# 01_NRF52.net
KiCad netlist of a schematic drawn in Altium Designer
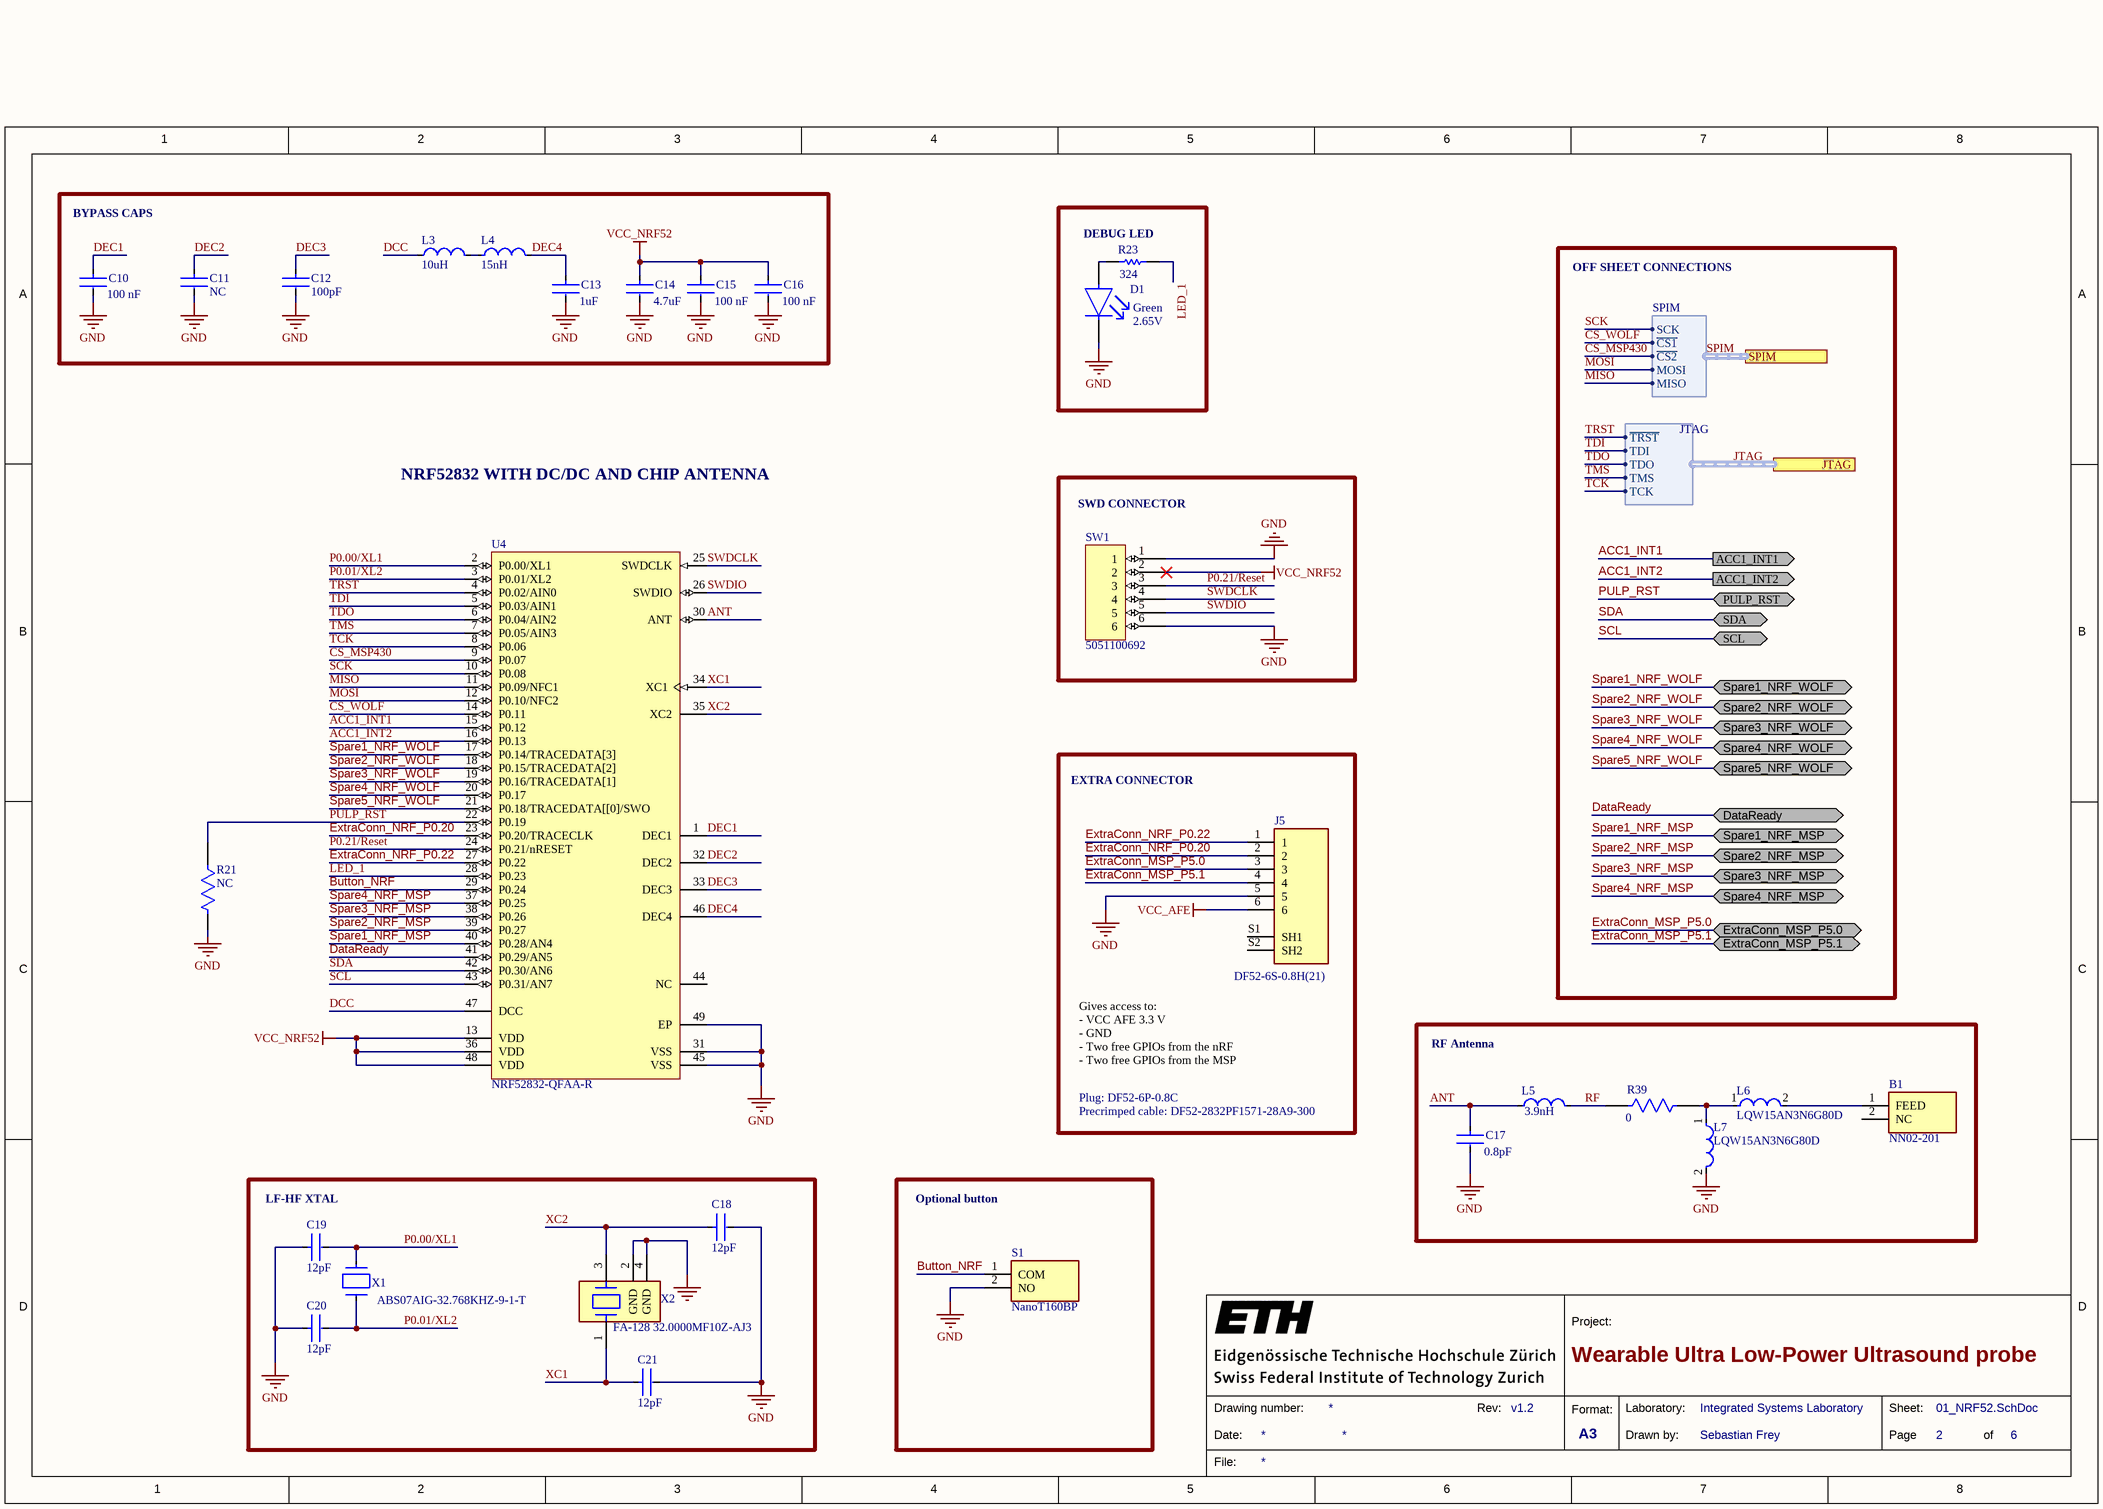
[diagram p0: 01_NRF52.SchDoc]

(export (version "E")
  (design (tool "Eeschema 10.0.6"))
  (components
    (comp (ref "B1")
      (value "NN02-201")
      (footprint "NN02201")
      (description "RF ANTENNA 2G, 3G, 4G, 5G, DCS, GSM, LTE, PCS, UMTS, Wifi DB Chip SMA Surface Mount")
      (fields (field (name "MOUSER PART NUMBER") "128-NN02-201"))
      (libsource (lib "Schlib1") (part "NN02-201"))
    )
    (comp (ref "C10")
      (value "100 nF")
      (footprint "FP-CC0402-MFG")
      (description "CAP CER 0.1UF 16V X7R 0402")
      (fields (field (name "MANUFACTURER") "YAGEO") (field (name "TOLERANCE") "0.1"))
      (libsource (lib "Altium Content Vault") (part "11868f565c42a9108669ba33697ecf6"))
    )
    (comp (ref "C11")
      (value "not mounted")
      (footprint "FP-04025A101JAT2A-MFG")
      (fields
        (field (name "TOLERANCE") "5%")
        (field (name "VOLTAGE") "50V")
        (field (name "CAPACITANCE") "NC")
      )
      (libsource (lib "Altium Content Vault") (part "f23184f103b6ebe33a8c269c53dcba6"))
    )
    (comp (ref "C12")
      (value "04025A101JAT2A")
      (footprint "FP-04025A101JAT2A-MFG")
      (description "CAP CER 100PF 50V C0G/NP0 0402")
      (fields
        (field (name "TOLERANCE") "5%")
        (field (name "VOLTAGE") "50V")
        (field (name "CAPACITANCE") "100pF")
      )
      (libsource (lib "Altium Content Vault") (part "f23184f103b6ebe33a8c269c53dcba6"))
    )
    (comp (ref "C13")
      (value "C1608X7R1C105K080AC")
      (footprint "FP-C1608-080-0_1-IPC_B")
      (description "Multilayer Ceramic Capacitors 1μF ±10% 16V X7R SMD 0603")
      (fields
        (field (name "VOLTAGE") "16V")
        (field (name "CAPACITANCE") "1uF")
        (field (name "TOLERANCE") "10%")
      )
      (libsource (lib "Altium Content Vault") (part "236180d848d6139a670b325ea6854c9"))
    )
    (comp (ref "C14")
      (value "EMK107ABJ475KA-T")
      (footprint "FP-0603-L_1_6_0_15-W_0_8-IPC_A")
      (description "None")
      (fields (field (name "CAPACITANCE") "4.7uF") (field (name "TOLERANCE") "10%"))
      (libsource (lib "Altium Content Vault") (part "11868f565c42a9108669ba33697ecf6"))
    )
    (comp (ref "C15")
      (value "100 nF")
      (footprint "FP-CC0402-MFG")
      (description "CAP CER 0.1UF 16V X7R 0402")
      (fields (field (name "MANUFACTURER") "YAGEO") (field (name "TOLERANCE") "0.1"))
      (libsource (lib "Altium Content Vault") (part "11868f565c42a9108669ba33697ecf6"))
    )
    (comp (ref "C16")
      (value "100 nF")
      (footprint "FP-CC0402-MFG")
      (description "CAP CER 0.1UF 16V X7R 0402")
      (fields (field (name "MANUFACTURER") "YAGEO") (field (name "TOLERANCE") "0.1"))
      (libsource (lib "Altium Content Vault") (part "11868f565c42a9108669ba33697ecf6"))
    )
    (comp (ref "C17")
      (value "GJM1555C1HR80WB01D")
      (footprint "FP-GJM155-0_05-IPC_A")
      (description "Multi-Layer Ceramic Capacitor 0.8pF C0G  ±0.05pF 0402 Paper T/R")
      (fields (field (name "CAPACITANCE") "0.8pF"))
      (libsource (lib "Altium Content Vault") (part "02cd4be3c70576c341d710602a673aa"))
    )
    (comp (ref "C18")
      (value "GJM1555C1H120GB01D")
      (footprint "FP-GJM155-0_05-IPC_A")
      (description "Multi-Layer Ceramic Capacitor 12pF C0G  ±2% 0402 Paper T/R")
      (fields (field (name "TOLERANCE") "2%") (field (name "CAPACITANCE") "12pF"))
      (libsource (lib "Altium Content Vault") (part "02cd4be3c70576c341d710602a673aa"))
    )
    (comp (ref "C19")
      (value "GJM1555C1H120GB01D")
      (footprint "FP-GJM155-0_05-IPC_A")
      (description "Multi-Layer Ceramic Capacitor 12pF C0G  ±2% 0402 Paper T/R")
      (fields (field (name "TOLERANCE") "2%") (field (name "CAPACITANCE") "12pF"))
      (libsource (lib "Altium Content Vault") (part "02cd4be3c70576c341d710602a673aa"))
    )
    (comp (ref "C20")
      (value "GJM1555C1H120GB01D")
      (footprint "FP-GJM155-0_05-IPC_A")
      (description "Multi-Layer Ceramic Capacitor 12pF C0G  ±2% 0402 Paper T/R")
      (fields (field (name "TOLERANCE") "2%") (field (name "CAPACITANCE") "12pF"))
      (libsource (lib "Altium Content Vault") (part "02cd4be3c70576c341d710602a673aa"))
    )
    (comp (ref "C21")
      (value "GJM1555C1H120GB01D")
      (footprint "FP-GJM155-0_05-IPC_A")
      (description "Multi-Layer Ceramic Capacitor 12pF C0G  ±2% 0402 Paper T/R")
      (fields (field (name "TOLERANCE") "2%") (field (name "CAPACITANCE") "12pF"))
      (libsource (lib "Altium Content Vault") (part "02cd4be3c70576c341d710602a673aa"))
    )
    (comp (ref "D1")
      (value "APHD1608LZGCK")
      (footprint "FP-APHD1608LZGCK-MFG")
      (description "LED GREEN CLEAR 1608 SMD")
      (fields (field (name "FORWARD VOLTAGE") "2.65V") (field (name "COLOR") "Green"))
      (libsource (lib "Altium Content Vault") (part "8706943c75ba83719d021d2fdc84c58"))
    )
    (comp (ref "J5")
      (value "DF52-6S-0.8H(21)")
      (footprint "PcbLib1:HIROSE_DF52-6S-0.8H(21)")
      (description "6 Position Socket Connector Surface Mount, Right Angle")
      (fields (field (name "MP") "DF52-6S-0.8H_21_") (field (name "MF") "Hirose"))
      (libsource (lib "Schlib1") (part "DF52-6S-0.8H(21)"))
    )
    (comp (ref "L3")
      (value "L0603B100KDWFT")
      (footprint "PcbLib1:L0603B100KDWFT")
      (description "Inductor RF Chip Wirewound 10uH 10% 2.52MHz 0.38A 0.36Ohm DCR 0603 T/R")
      (fields
        (field (name "MANUFACTURER") "KEMET")
        (field (name "TOLERANCE") "10%")
        (field (name "INDUCTANCE") "10uH")
      )
      (libsource (lib "Schlib1") (part "L0603B100KDWFT"))
    )
    (comp (ref "L4")
      (value "LQW15AN15NJ00D")
      (footprint "FP-LQW15AN_00-W0_6-0_1-MFG")
      (description "Wire Wound RF Inductor 15nH ±5% 460mA 0.16Ω 0402 (1005)")
      (fields (field (name "INDUCTANCE") "15nH") (field (name "TOLERANCE") "5%"))
      (libsource (lib "Altium Content Vault") (part "725321dda6339637d4d059423bc1c3c"))
    )
    (comp (ref "L5")
      (value "LQG15HS3N9B02D")
      (footprint "PcbLib1:INDC1005X45N")
      (description "Inductor RF Chip Thin Film 3.9nH 0.1nH 500MHz 13Q-Factor 170mA 500mOhm DCR 0402 Paper T/R")
      (fields
        (field (name "MANUFACTURER") "Murata")
        (field (name "MANUFACTURER PART NUMBER") "LQP15MN3N9B02D")
        (field (name "INDUCTANCE") "3.9nH")
      )
      (libsource (lib "Schlib1") (part "LQP15MN3N9B02D"))
    )
    (comp (ref "L6")
      (value "LQW15AN3N6G80D")
      (footprint "PcbLib1:Component_0402_0603")
      (description "Wire Wound RF Inductor 3.6nH ±2% 1950mA 0.03Ω 0402 (1005)")
      (libsource (lib "Schlib1") (part "725321dda6339637d4d059423bc1c3c"))
    )
    (comp (ref "L7")
      (value "LQW15AN3N6G80D")
      (footprint "PcbLib1:Component_0402_0603")
      (description "Wire Wound RF Inductor 3.6nH ±2% 1950mA 0.03Ω 0402 (1005)")
      (libsource (lib "Schlib1") (part "725321dda6339637d4d059423bc1c3c"))
    )
    (comp (ref "R21")
      (value "~")
      (footprint "FP-ERJ2RK-IPC_C")
      (description "not mounted")
      (fields (field (name "RESISTANCE") "NC") (field (name "TOLERANCE") "1%"))
      (libsource (lib "Altium Content Vault") (part "1029c3af85768c4190bb7ad29bc67b5"))
    )
    (comp (ref "R23")
      (value "CPF0402B324RE1")
      (footprint "RESC1005X35X20ML05T10")
      (fields (field (name "MANUFACTURER") "TE Connectivity / AMP") (field (name "RESISTANCE") "324"))
      (libsource (lib "Altium Content Vault") (part "RES"))
    )
    (comp (ref "R39")
      (value "CR0402-J/-000GLF")
      (footprint "PcbLib1:Component_0402_0603")
      (description "Thick Film Chip Resistors 0402 0Ω 0.0625W 5%")
      (fields (field (name "TOLERANCE") "5%") (field (name "RESISTANCE") "0"))
      (libsource (lib "Schlib1") (part "1029c3af85768c4190bb7ad29bc67b5"))
    )
    (comp (ref "S1")
      (value "NanoT160BP")
      (footprint "PcbLib1:NanoT160BP")
      (description "Switch")
      (libsource (lib "Schlib1") (part "NanoT160BP"))
    )
    (comp (ref "SW1")
      (value "5051100692")
      (footprint "PcbLib1:MOLEX_5051100692")
      (libsource (lib "Schlib1") (part "MOLEX_5051100692"))
    )
    (comp (ref "U4")
      (value "NRF52832-QFAA-R")
      (footprint "NRSC-QF-48_M")
      (fields (field (name "MANUFACTURER") "Nordic Semiconductor"))
      (libsource (lib "Altium Content Vault") (part "NRSC-NRF52832-QF-48"))
    )
    (comp (ref "X1")
      (value "ABS07AIG-32.768KHZ-9-1-T")
      (footprint "PcbLib1:Crys_Abracon_ABS07AIG-32_768KHZ-9-1-T_eec_MFG")
      (description "Crystal")
      (libsource (lib "Schlib1") (part "Crys_Abracon_ABS07AIG-32_768KHZ-9-1-T_eec"))
    )
    (comp (ref "X2")
      (value "FA-128 32.0000MF10Z-AJ3")
      (footprint "PcbLib1:Crys_Seiko_Epson_Corporation_FA-128_32.0000MF10Z-AJ3_eec_0")
      (description "Crystal")
      (fields (field (name "PART NR") "FA-128 32.0000MF10Z-AJ3"))
      (libsource (lib "Schlib1") (part "Crys_Seiko_Epson_Corporation_FA-128_32.0000MF10Z-AJ3_eec"))
    )
  )
  (nets
    (net (code "3") (name "/ACC1_INT1") (class "Default")
      (node (ref "U4") (pin "15") (pinfunction "P0.12_15") (pintype "bidirectional"))
    )
    (net (code "4") (name "/ACC1_INT2") (class "Default")
      (node (ref "U4") (pin "16") (pinfunction "P0.13_16") (pintype "bidirectional"))
    )
    (net (code "5") (name "/ANT") (class "Default")
      (node (ref "C17") (pin "1") (pinfunction "1_1") (pintype "passive"))
      (node (ref "L5") (pin "1") (pinfunction "1_1") (pintype "passive"))
      (node (ref "U4") (pin "30") (pinfunction "ANT_30") (pintype "bidirectional"))
    )
    (net (code "6") (name "/Button_NRF") (class "Default")
      (node (ref "S1") (pin "1") (pinfunction "COM_1") (pintype "passive"))
      (node (ref "U4") (pin "29") (pinfunction "P0.24_29") (pintype "bidirectional"))
    )
    (net (code "7") (name "/CS_MSP430") (class "Default")
      (node (ref "U4") (pin "9") (pinfunction "P0.07_9") (pintype "bidirectional"))
    )
    (net (code "8") (name "/CS_WOLF") (class "Default")
      (node (ref "U4") (pin "14") (pinfunction "P0.11_14") (pintype "bidirectional"))
    )
    (net (code "9") (name "/DCC") (class "Default")
      (node (ref "L3") (pin "1") (pinfunction "1_1") (pintype "passive"))
      (node (ref "U4") (pin "47") (pinfunction "DCC_47") (pintype "power_in"))
    )
    (net (code "10") (name "/DEC1") (class "Default")
      (node (ref "C10") (pin "1") (pinfunction "1_1") (pintype "passive"))
      (node (ref "U4") (pin "1") (pinfunction "DEC1_1") (pintype "passive"))
    )
    (net (code "11") (name "/DEC2") (class "Default")
      (node (ref "C11") (pin "2") (pinfunction "2_2") (pintype "passive"))
      (node (ref "U4") (pin "32") (pinfunction "DEC2_32") (pintype "passive"))
    )
    (net (code "12") (name "/DEC3") (class "Default")
      (node (ref "C12") (pin "2") (pinfunction "2_2") (pintype "passive"))
      (node (ref "U4") (pin "33") (pinfunction "DEC3_33") (pintype "passive"))
    )
    (net (code "13") (name "/DEC4") (class "Default")
      (node (ref "C13") (pin "2") (pinfunction "2_2") (pintype "passive"))
      (node (ref "L4") (pin "2") (pinfunction "2_2") (pintype "passive"))
      (node (ref "U4") (pin "46") (pinfunction "DEC4_46") (pintype "passive"))
    )
    (net (code "14") (name "/DataReady") (class "Default")
      (node (ref "U4") (pin "41") (pinfunction "P0.29/AN5_41") (pintype "bidirectional"))
    )
    (net (code "15") (name "/ExtraConn_MSP_P5.0") (class "Default")
      (node (ref "J5") (pin "3") (pinfunction "3_3") (pintype "passive"))
    )
    (net (code "16") (name "/ExtraConn_MSP_P5.1") (class "Default")
      (node (ref "J5") (pin "4") (pinfunction "4_4") (pintype "passive"))
    )
    (net (code "17") (name "/ExtraConn_NRF_P0.20") (class "Default")
      (node (ref "J5") (pin "2") (pinfunction "2_2") (pintype "passive"))
      (node (ref "U4") (pin "23") (pinfunction "P0.20/TRACECLK_23") (pintype "bidirectional"))
    )
    (net (code "18") (name "/ExtraConn_NRF_P0.22") (class "Default")
      (node (ref "J5") (pin "1") (pinfunction "1_1") (pintype "passive"))
      (node (ref "U4") (pin "27") (pinfunction "P0.22_27") (pintype "bidirectional"))
    )
    (net (code "20") (name "/LED_1") (class "Default")
      (node (ref "R23") (pin "1") (pinfunction "1_1") (pintype "passive"))
      (node (ref "U4") (pin "28") (pinfunction "P0.23_28") (pintype "bidirectional"))
    )
    (net (code "21") (name "/MISO") (class "Default")
      (node (ref "U4") (pin "11") (pinfunction "P0.09/NFC1_11") (pintype "bidirectional"))
    )
    (net (code "22") (name "/MOSI") (class "Default")
      (node (ref "U4") (pin "12") (pinfunction "P0.10/NFC2_12") (pintype "bidirectional"))
    )
    (net (code "23") (name "/P0.00{slash}XL1") (class "Default")
      (node (ref "C19") (pin "2") (pinfunction "2_2") (pintype "passive"))
      (node (ref "U4") (pin "2") (pinfunction "P0.00/XL1_2") (pintype "bidirectional"))
      (node (ref "X1") (pin "1") (pinfunction "1_1") (pintype "passive"))
    )
    (net (code "24") (name "/P0.01{slash}XL2") (class "Default")
      (node (ref "C20") (pin "2") (pinfunction "2_2") (pintype "passive"))
      (node (ref "U4") (pin "3") (pinfunction "P0.01/XL2_3") (pintype "bidirectional"))
      (node (ref "X1") (pin "2") (pinfunction "2_2") (pintype "passive"))
    )
    (net (code "25") (name "/P0.21{slash}Reset") (class "Default")
      (node (ref "SW1") (pin "3") (pinfunction "3_3") (pintype "bidirectional"))
      (node (ref "U4") (pin "24") (pinfunction "P0.21/nRESET_24") (pintype "bidirectional"))
    )
    (net (code "26") (name "/PULP_RST") (class "Default")
      (node (ref "R21") (pin "1") (pinfunction "1_1") (pintype "passive"))
      (node (ref "U4") (pin "22") (pinfunction "P0.19_22") (pintype "bidirectional"))
    )
    (net (code "27") (name "/RF") (class "Default")
      (node (ref "L5") (pin "2") (pinfunction "2_2") (pintype "passive"))
      (node (ref "R39") (pin "1") (pinfunction "1_1") (pintype "passive"))
    )
    (net (code "28") (name "/SCK") (class "Default")
      (node (ref "U4") (pin "10") (pinfunction "P0.08_10") (pintype "bidirectional"))
    )
    (net (code "29") (name "/SCL") (class "Default")
      (node (ref "U4") (pin "43") (pinfunction "P0.31/AN7_43") (pintype "bidirectional"))
    )
    (net (code "30") (name "/SDA") (class "Default")
      (node (ref "U4") (pin "42") (pinfunction "P0.30/AN6_42") (pintype "bidirectional"))
    )
    (net (code "32") (name "/SWDCLK") (class "Default")
      (node (ref "SW1") (pin "4") (pinfunction "4_4") (pintype "bidirectional"))
      (node (ref "U4") (pin "25") (pinfunction "SWDCLK_25") (pintype "input"))
    )
    (net (code "33") (name "/SWDIO") (class "Default")
      (node (ref "SW1") (pin "5") (pinfunction "5_5") (pintype "bidirectional"))
      (node (ref "U4") (pin "26") (pinfunction "SWDIO_26") (pintype "bidirectional"))
    )
    (net (code "34") (name "/Spare1_NRF_MSP") (class "Default")
      (node (ref "U4") (pin "40") (pinfunction "P0.28/AN4_40") (pintype "bidirectional"))
    )
    (net (code "35") (name "/Spare1_NRF_WOLF") (class "Default")
      (node (ref "U4") (pin "17") (pinfunction "P0.14/TRACEDATA[3]_17") (pintype "bidirectional"))
    )
    (net (code "36") (name "/Spare2_NRF_MSP") (class "Default")
      (node (ref "U4") (pin "39") (pinfunction "P0.27_39") (pintype "bidirectional"))
    )
    (net (code "37") (name "/Spare2_NRF_WOLF") (class "Default")
      (node (ref "U4") (pin "18") (pinfunction "P0.15/TRACEDATA[2]_18") (pintype "bidirectional"))
    )
    (net (code "38") (name "/Spare3_NRF_MSP") (class "Default")
      (node (ref "U4") (pin "38") (pinfunction "P0.26_38") (pintype "bidirectional"))
    )
    (net (code "39") (name "/Spare3_NRF_WOLF") (class "Default")
      (node (ref "U4") (pin "19") (pinfunction "P0.16/TRACEDATA[1]_19") (pintype "bidirectional"))
    )
    (net (code "40") (name "/Spare4_NRF_MSP") (class "Default")
      (node (ref "U4") (pin "37") (pinfunction "P0.25_37") (pintype "bidirectional"))
    )
    (net (code "41") (name "/Spare4_NRF_WOLF") (class "Default")
      (node (ref "U4") (pin "20") (pinfunction "P0.17_20") (pintype "bidirectional"))
    )
    (net (code "42") (name "/Spare5_NRF_WOLF") (class "Default")
      (node (ref "U4") (pin "21") (pinfunction "P0.18/TRACEDATA[[0]/SWO_21") (pintype "bidirectional"))
    )
    (net (code "43") (name "/TCK") (class "Default")
      (node (ref "U4") (pin "8") (pinfunction "P0.06_8") (pintype "bidirectional"))
    )
    (net (code "44") (name "/TDI") (class "Default")
      (node (ref "U4") (pin "5") (pinfunction "P0.03/AIN1_5") (pintype "bidirectional"))
    )
    (net (code "45") (name "/TDO") (class "Default")
      (node (ref "U4") (pin "6") (pinfunction "P0.04/AIN2_6") (pintype "bidirectional"))
    )
    (net (code "46") (name "/TMS") (class "Default")
      (node (ref "U4") (pin "7") (pinfunction "P0.05/AIN3_7") (pintype "bidirectional"))
    )
    (net (code "47") (name "/TRST") (class "Default")
      (node (ref "U4") (pin "4") (pinfunction "P0.02/AIN0_4") (pintype "bidirectional"))
    )
    (net (code "48") (name "/XC1") (class "Default")
      (node (ref "C21") (pin "1") (pinfunction "1_1") (pintype "passive"))
      (node (ref "U4") (pin "34") (pinfunction "XC1_34") (pintype "input"))
      (node (ref "X2") (pin "1") (pinfunction "1_1") (pintype "passive"))
    )
    (net (code "49") (name "/XC2") (class "Default")
      (node (ref "C18") (pin "1") (pinfunction "1_1") (pintype "passive"))
      (node (ref "U4") (pin "35") (pinfunction "XC2_35") (pintype "passive"))
      (node (ref "X2") (pin "3") (pinfunction "3_3") (pintype "passive"))
    )
    (net (code "50") (name "GND") (class "Default")
      (node (ref "C10") (pin "2") (pinfunction "2_2") (pintype "passive"))
      (node (ref "C11") (pin "1") (pinfunction "1_1") (pintype "passive"))
      (node (ref "C12") (pin "1") (pinfunction "1_1") (pintype "passive"))
      (node (ref "C13") (pin "1") (pinfunction "1_1") (pintype "passive"))
      (node (ref "C14") (pin "2") (pinfunction "2_2") (pintype "passive"))
      (node (ref "C15") (pin "2") (pinfunction "2_2") (pintype "passive"))
      (node (ref "C16") (pin "2") (pinfunction "2_2") (pintype "passive"))
      (node (ref "C17") (pin "2") (pinfunction "2_2") (pintype "passive"))
      (node (ref "C18") (pin "2") (pinfunction "2_2") (pintype "passive"))
      (node (ref "C19") (pin "1") (pinfunction "1_1") (pintype "passive"))
      (node (ref "C20") (pin "1") (pinfunction "1_1") (pintype "passive"))
      (node (ref "C21") (pin "2") (pinfunction "2_2") (pintype "passive"))
      (node (ref "D1") (pin "1") (pinfunction "C_1") (pintype "passive"))
      (node (ref "J5") (pin "5") (pinfunction "5_5") (pintype "passive"))
      (node (ref "L7") (pin "2") (pinfunction "2_2") (pintype "passive"))
      (node (ref "R21") (pin "2") (pinfunction "2_2") (pintype "passive"))
      (node (ref "S1") (pin "2") (pinfunction "NO_2") (pintype "passive"))
      (node (ref "SW1") (pin "1") (pinfunction "1_1") (pintype "bidirectional"))
      (node (ref "SW1") (pin "6") (pinfunction "6_6") (pintype "bidirectional"))
      (node (ref "U4") (pin "31") (pinfunction "VSS_31") (pintype "power_in"))
      (node (ref "U4") (pin "45") (pinfunction "VSS_45") (pintype "power_in"))
      (node (ref "U4") (pin "49") (pinfunction "EP_49") (pintype "power_in"))
      (node (ref "X2") (pin "2") (pinfunction "GND_2") (pintype "passive"))
      (node (ref "X2") (pin "4") (pinfunction "GND_4") (pintype "passive"))
    )
    (net (code "51") (name "Net-(B1-FEED)") (class "Default")
      (node (ref "B1") (pin "1") (pinfunction "FEED_1") (pintype "passive"))
      (node (ref "L6") (pin "2") (pinfunction "2_2") (pintype "passive"))
    )
    (net (code "52") (name "Net-(D1-A)") (class "Default")
      (node (ref "D1") (pin "2") (pinfunction "A_2") (pintype "passive"))
      (node (ref "R23") (pin "2") (pinfunction "2_2") (pintype "passive"))
    )
    (net (code "53") (name "Net-(L3-Pad2)") (class "Default")
      (node (ref "L3") (pin "2") (pinfunction "2_2") (pintype "passive"))
      (node (ref "L4") (pin "1") (pinfunction "1_1") (pintype "passive"))
    )
    (net (code "54") (name "Net-(L6-Pad1)") (class "Default")
      (node (ref "L6") (pin "1") (pinfunction "1_1") (pintype "passive"))
      (node (ref "L7") (pin "1") (pinfunction "1_1") (pintype "passive"))
      (node (ref "R39") (pin "2") (pinfunction "2_2") (pintype "passive"))
    )
    (net (code "55") (name "VCC_AFE") (class "Default")
      (node (ref "J5") (pin "6") (pinfunction "6_6") (pintype "passive"))
    )
    (net (code "56") (name "VCC_NRF52") (class "Default")
      (node (ref "C14") (pin "1") (pinfunction "1_1") (pintype "passive"))
      (node (ref "C15") (pin "1") (pinfunction "1_1") (pintype "passive"))
      (node (ref "C16") (pin "1") (pinfunction "1_1") (pintype "passive"))
      (node (ref "SW1") (pin "2") (pinfunction "2_2") (pintype "bidirectional"))
      (node (ref "U4") (pin "13") (pinfunction "VDD_13") (pintype "power_in"))
      (node (ref "U4") (pin "36") (pinfunction "VDD_36") (pintype "power_in"))
      (node (ref "U4") (pin "48") (pinfunction "VDD_48") (pintype "power_in"))
    )
    (net (code "57") (name "unconnected-(B1-NC-Pad2)") (class "Default")
      (node (ref "B1") (pin "2") (pinfunction "NC_2") (pintype "passive"))
    )
    (net (code "58") (name "unconnected-(J5-SH1-PadS1)") (class "Default")
      (node (ref "J5") (pin "S1") (pinfunction "SH1_S1") (pintype "passive"))
    )
    (net (code "59") (name "unconnected-(J5-SH2-PadS2)") (class "Default")
      (node (ref "J5") (pin "S2") (pinfunction "SH2_S2") (pintype "passive"))
    )
    (net (code "60") (name "unconnected-(U4-NC-Pad44)") (class "Default")
      (node (ref "U4") (pin "44") (pinfunction "NC_44") (pintype "passive"))
    )
  )
)
